# stm32_mcu.net
KiCad netlist of a schematic drawn in Altium Designer
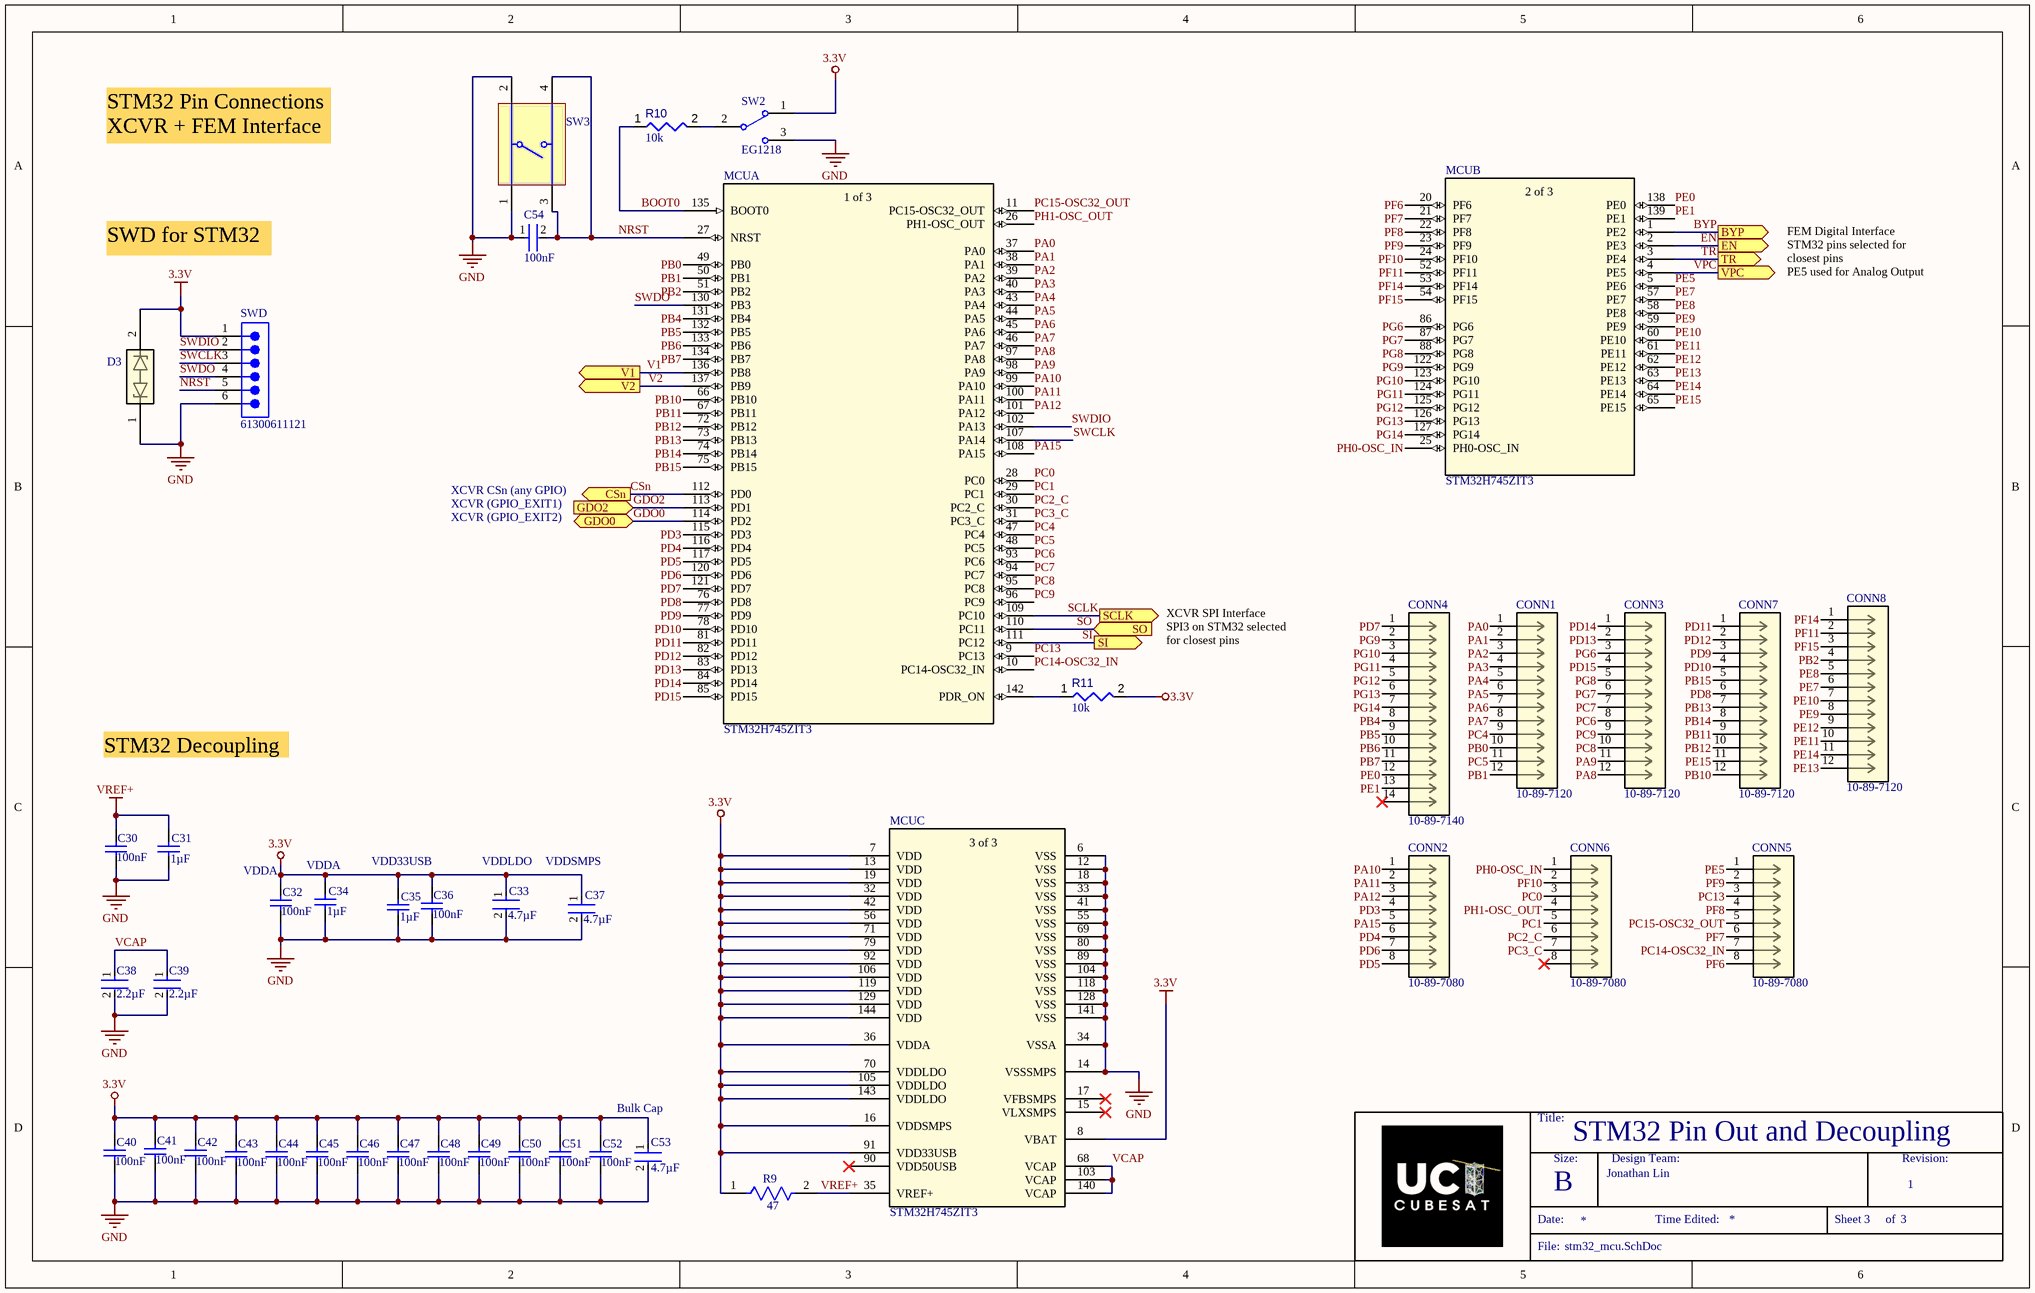
[diagram p0: stm32_mcu.SchDoc]

(export (version "E")
  (design (tool "Eeschema 10.0.6"))
  (components
    (comp (ref "C30")
      (value "100nF")
      (footprint "CAPC2013X135X45ML10T25")
      (fields (field (name "Comment") "GRM21BR72A104KAC4L"))
      (libsource (lib "University of California Irvine") (part "CAP"))
    )
    (comp (ref "C31")
      (value "1µF")
      (footprint "CAPC2013X135X45LL10T25")
      (fields (field (name "Comment") "GRM21BR71C105KA01L"))
      (libsource (lib "University of California Irvine") (part "CAP-NP-2"))
    )
    (comp (ref "C32")
      (value "100nF")
      (footprint "CAPC2013X135X45ML10T25")
      (fields (field (name "Comment") "GRM21BR72A104KAC4L"))
      (libsource (lib "University of California Irvine") (part "CAP"))
    )
    (comp (ref "C33")
      (value "4.7µF")
      (footprint "FP-GRM21B-0_2-e0_2_0_7-MFG")
      (fields (field (name "Comment") "GRM21BZ7YA475KE15K"))
      (libsource (lib "University of California Irvine") (part "b4654b650e69147ec39a6b967a45e02"))
    )
    (comp (ref "C34")
      (value "1µF")
      (footprint "CAPC2013X135X45LL10T25")
      (fields (field (name "Comment") "GRM21BR71C105KA01L"))
      (libsource (lib "University of California Irvine") (part "CAP-NP-2"))
    )
    (comp (ref "C35")
      (value "1µF")
      (footprint "CAPC2013X135X45LL10T25")
      (fields (field (name "Comment") "GRM21BR71C105KA01L"))
      (libsource (lib "University of California Irvine") (part "CAP-NP-2"))
    )
    (comp (ref "C36")
      (value "100nF")
      (footprint "CAPC2013X135X45ML10T25")
      (fields (field (name "Comment") "GRM21BR72A104KAC4L"))
      (libsource (lib "University of California Irvine") (part "CAP"))
    )
    (comp (ref "C37")
      (value "4.7µF")
      (footprint "FP-GRM21B-0_2-e0_2_0_7-MFG")
      (fields (field (name "Comment") "GRM21BZ7YA475KE15K"))
      (libsource (lib "University of California Irvine") (part "b4654b650e69147ec39a6b967a45e02"))
    )
    (comp (ref "C38")
      (value "2.2µF")
      (footprint "FP-GRM21B-0_15-IPC_A")
      (fields (field (name "Comment") "GRM21BR71E225KE11L"))
      (libsource (lib "University of California Irvine") (part "b4654b650e69147ec39a6b967a45e02"))
    )
    (comp (ref "C39")
      (value "2.2µF")
      (footprint "FP-GRM21B-0_15-IPC_A")
      (fields (field (name "Comment") "GRM21BR71E225KE11L"))
      (libsource (lib "University of California Irvine") (part "b4654b650e69147ec39a6b967a45e02"))
    )
    (comp (ref "C40")
      (value "100nF")
      (footprint "CAPC2013X135X45ML10T25")
      (fields (field (name "Comment") "GRM21BR72A104KAC4L"))
      (libsource (lib "University of California Irvine") (part "CAP"))
    )
    (comp (ref "C41")
      (value "100nF")
      (footprint "CAPC2013X135X45ML10T25")
      (fields (field (name "Comment") "GRM21BR72A104KAC4L"))
      (libsource (lib "University of California Irvine") (part "CAP"))
    )
    (comp (ref "C42")
      (value "100nF")
      (footprint "CAPC2013X135X45ML10T25")
      (fields (field (name "Comment") "GRM21BR72A104KAC4L"))
      (libsource (lib "University of California Irvine") (part "CAP"))
    )
    (comp (ref "C43")
      (value "100nF")
      (footprint "CAPC2013X135X45ML10T25")
      (fields (field (name "Comment") "GRM21BR72A104KAC4L"))
      (libsource (lib "University of California Irvine") (part "CAP"))
    )
    (comp (ref "C44")
      (value "100nF")
      (footprint "CAPC2013X135X45ML10T25")
      (fields (field (name "Comment") "GRM21BR72A104KAC4L"))
      (libsource (lib "University of California Irvine") (part "CAP"))
    )
    (comp (ref "C45")
      (value "100nF")
      (footprint "CAPC2013X135X45ML10T25")
      (fields (field (name "Comment") "GRM21BR72A104KAC4L"))
      (libsource (lib "University of California Irvine") (part "CAP"))
    )
    (comp (ref "C46")
      (value "100nF")
      (footprint "CAPC2013X135X45ML10T25")
      (fields (field (name "Comment") "GRM21BR72A104KAC4L"))
      (libsource (lib "University of California Irvine") (part "CAP"))
    )
    (comp (ref "C47")
      (value "100nF")
      (footprint "CAPC2013X135X45ML10T25")
      (fields (field (name "Comment") "GRM21BR72A104KAC4L"))
      (libsource (lib "University of California Irvine") (part "CAP"))
    )
    (comp (ref "C48")
      (value "100nF")
      (footprint "CAPC2013X135X45ML10T25")
      (fields (field (name "Comment") "GRM21BR72A104KAC4L"))
      (libsource (lib "University of California Irvine") (part "CAP"))
    )
    (comp (ref "C49")
      (value "100nF")
      (footprint "CAPC2013X135X45ML10T25")
      (fields (field (name "Comment") "GRM21BR72A104KAC4L"))
      (libsource (lib "University of California Irvine") (part "CAP"))
    )
    (comp (ref "C50")
      (value "100nF")
      (footprint "CAPC2013X135X45ML10T25")
      (fields (field (name "Comment") "GRM21BR72A104KAC4L"))
      (libsource (lib "University of California Irvine") (part "CAP"))
    )
    (comp (ref "C51")
      (value "100nF")
      (footprint "CAPC2013X135X45ML10T25")
      (fields (field (name "Comment") "GRM21BR72A104KAC4L"))
      (libsource (lib "University of California Irvine") (part "CAP"))
    )
    (comp (ref "C52")
      (value "100nF")
      (footprint "CAPC2013X135X45ML10T25")
      (fields (field (name "Comment") "GRM21BR72A104KAC4L"))
      (libsource (lib "University of California Irvine") (part "CAP"))
    )
    (comp (ref "C53")
      (value "4.7µF")
      (footprint "FP-GRM21B-0_2-e0_2_0_7-MFG")
      (fields (field (name "Comment") "GRM21BZ7YA475KE15K"))
      (libsource (lib "University of California Irvine") (part "b4654b650e69147ec39a6b967a45e02"))
    )
    (comp (ref "C54")
      (value "100nF")
      (footprint "FP-C0805C-DN-IPC_A")
      (fields (field (name "Comment") "C0805C104K5RACTU"))
      (libsource (lib "University of California Irvine") (part "b4654b650e69147ec39a6b967a45e02"))
    )
    (comp (ref "CONN1")
      (value "10-89-7120")
      (footprint "CONN12_0010897120_MOL")
      (libsource (lib "University of California Irvine") (part "10-89-7120-Symbol-1"))
    )
    (comp (ref "CONN2")
      (value "10-89-7080")
      (footprint "CONN08_0010897080_MOL")
      (libsource (lib "University of California Irvine") (part "10-89-7080-Symbol-1"))
    )
    (comp (ref "CONN3")
      (value "10-89-7120")
      (footprint "CONN12_0010897120_MOL")
      (libsource (lib "University of California Irvine") (part "10-89-7120-Symbol-1"))
    )
    (comp (ref "CONN4")
      (value "10-89-7140")
      (footprint "CONN14_0010897140_MOL")
      (libsource (lib "University of California Irvine") (part "10-89-7140-Symbol-1"))
    )
    (comp (ref "CONN5")
      (value "10-89-7080")
      (footprint "CONN08_0010897080_MOL")
      (libsource (lib "University of California Irvine") (part "10-89-7080-Symbol-1"))
    )
    (comp (ref "CONN6")
      (value "10-89-7080")
      (footprint "CONN08_0010897080_MOL")
      (libsource (lib "University of California Irvine") (part "10-89-7080-Symbol-1"))
    )
    (comp (ref "CONN7")
      (value "10-89-7120")
      (footprint "CONN12_0010897120_MOL")
      (libsource (lib "University of California Irvine") (part "10-89-7120-Symbol-1"))
    )
    (comp (ref "CONN8")
      (value "10-89-7120")
      (footprint "CONN12_0010897120_MOL")
      (libsource (lib "University of California Irvine") (part "10-89-7120-Symbol-1"))
    )
    (comp (ref "D3")
      (value "PESD3V3Z1BCSFYL")
      (footprint "SOD962-2_DSN0603-2_NEX")
      (description "PESD3V3Zxx: 6.8 V 15 A 0.45 pF Bidirectional ESD Protection Diode - DSN0603-2")
      (libsource (lib "University of California Irvine") (part "PESD3V3Z1BCSFYL-Symbol-1"))
    )
    (comp (ref "MCU")
      (value "STM32H745ZIT3")
      (footprint "LQFP-144")
      (description "No Description Available")
      (libsource (lib "University of California Irvine") (part "STM32H745ZIT3"))
    )
    (comp (ref "R9")
      (value "47")
      (footprint "FP-RMCF1206-IPC_B")
      (fields
        (field (name "POWER") "250mW")
        (field (name "TOLERANCE") "5%")
        (field (name "Comment") "RMCF1206JT47R0")
      )
      (libsource (lib "University of California Irvine") (part "1029c3af85768c4190bb7ad29bc67b5"))
    )
    (comp (ref "R10")
      (value "10k")
      (footprint "RESC3216X60X45ML15T20")
      (fields
        (field (name "TOLERANCE") "1%")
        (field (name "POWER") "250mW")
        (field (name "Comment") "RC0805FR-0710KL")
      )
      (libsource (lib "University of California Irvine") (part "RES-2"))
    )
    (comp (ref "R11")
      (value "10k")
      (footprint "RESC3216X60X45ML15T20")
      (description "Chip Resistor, 10 KOhm, +/- 1%, 0.25 W, -55 to 155 degC, 1206 (3216 Metric)")
      (fields (field (name "TOLERANCE") "1%") (field (name "POWER") "250mW"))
      (libsource (lib "University of California Irvine") (part "RES-2"))
    )
    (comp (ref "SW2")
      (value "EG1218")
      (footprint "ESWI-EG1218_V")
      (description "Slide Switch, SPDT, 500 V, -20 to 70 degC, 3-Pin THD, RoHS, Bulk")
      (fields (field (name "MANUFACTURER") "E-Switch"))
      (libsource (lib "University of California Irvine") (part "SW-SPDT-3_B"))
    )
    (comp (ref "SW3")
      (value "1825910-6 Tact Switch")
      (footprint "TECO-1825910-6_V")
      (libsource (lib "University of California Irvine") (part "SW-SPST-4_A"))
    )
    (comp (ref "SWD")
      (value "61300611121")
      (footprint "61300611121")
      (libsource (lib "University of California Irvine") (part "Header_Male_1R_06P"))
    )
  )
  (nets
    (net (code "1") (name "/BOOT0") (class "Default")
      (node (ref "MCU") (pin "135") (pinfunction "BOOT0_135") (pintype "input"))
      (node (ref "R10") (pin "1") (pinfunction "1_1") (pintype "passive"))
    )
    (net (code "2") (name "/BYP") (class "Default")
      (node (ref "MCU") (pin "1") (pinfunction "PE2_1") (pintype "bidirectional"))
    )
    (net (code "3") (name "/CSn") (class "Default")
      (node (ref "MCU") (pin "112") (pinfunction "PD0_112") (pintype "bidirectional"))
    )
    (net (code "4") (name "/EN") (class "Default")
      (node (ref "MCU") (pin "2") (pinfunction "PE3_2") (pintype "bidirectional"))
    )
    (net (code "5") (name "/GDO0") (class "Default")
      (node (ref "MCU") (pin "114") (pinfunction "PD2_114") (pintype "bidirectional"))
    )
    (net (code "6") (name "/GDO2") (class "Default")
      (node (ref "MCU") (pin "113") (pinfunction "PD1_113") (pintype "bidirectional"))
    )
    (net (code "7") (name "/NRST") (class "Default")
      (node (ref "C54") (pin "2") (pinfunction "2_2") (pintype "passive"))
      (node (ref "MCU") (pin "27") (pinfunction "NRST_27") (pintype "bidirectional"))
      (node (ref "SW3") (pin "3") (pinfunction "3_3") (pintype "passive"))
      (node (ref "SW3") (pin "4") (pinfunction "4_4") (pintype "passive"))
      (node (ref "SWD") (pin "5") (pinfunction "5_5") (pintype "passive"))
    )
    (net (code "8") (name "/PA0") (class "Default")
      (node (ref "CONN1") (pin "1") (pinfunction "1_1") (pintype "passive"))
      (node (ref "MCU") (pin "37") (pinfunction "PA0_37") (pintype "bidirectional"))
    )
    (net (code "9") (name "/PA1") (class "Default")
      (node (ref "CONN1") (pin "2") (pinfunction "2_2") (pintype "passive"))
      (node (ref "MCU") (pin "38") (pinfunction "PA1_38") (pintype "bidirectional"))
    )
    (net (code "10") (name "/PA2") (class "Default")
      (node (ref "CONN1") (pin "3") (pinfunction "3_3") (pintype "passive"))
      (node (ref "MCU") (pin "39") (pinfunction "PA2_39") (pintype "bidirectional"))
    )
    (net (code "11") (name "/PA3") (class "Default")
      (node (ref "CONN1") (pin "4") (pinfunction "4_4") (pintype "passive"))
      (node (ref "MCU") (pin "40") (pinfunction "PA3_40") (pintype "bidirectional"))
    )
    (net (code "12") (name "/PA4") (class "Default")
      (node (ref "CONN1") (pin "5") (pinfunction "5_5") (pintype "passive"))
      (node (ref "MCU") (pin "43") (pinfunction "PA4_43") (pintype "bidirectional"))
    )
    (net (code "13") (name "/PA5") (class "Default")
      (node (ref "CONN1") (pin "6") (pinfunction "6_6") (pintype "passive"))
      (node (ref "MCU") (pin "44") (pinfunction "PA5_44") (pintype "bidirectional"))
    )
    (net (code "14") (name "/PA6") (class "Default")
      (node (ref "CONN1") (pin "7") (pinfunction "7_7") (pintype "passive"))
      (node (ref "MCU") (pin "45") (pinfunction "PA6_45") (pintype "bidirectional"))
    )
    (net (code "15") (name "/PA7") (class "Default")
      (node (ref "CONN1") (pin "8") (pinfunction "8_8") (pintype "passive"))
      (node (ref "MCU") (pin "46") (pinfunction "PA7_46") (pintype "bidirectional"))
    )
    (net (code "16") (name "/PA8") (class "Default")
      (node (ref "CONN3") (pin "12") (pinfunction "12_12") (pintype "passive"))
      (node (ref "MCU") (pin "97") (pinfunction "PA8_97") (pintype "bidirectional"))
    )
    (net (code "17") (name "/PA9") (class "Default")
      (node (ref "CONN3") (pin "11") (pinfunction "11_11") (pintype "passive"))
      (node (ref "MCU") (pin "98") (pinfunction "PA9_98") (pintype "bidirectional"))
    )
    (net (code "18") (name "/PA10") (class "Default")
      (node (ref "CONN2") (pin "1") (pinfunction "1_1") (pintype "passive"))
      (node (ref "MCU") (pin "99") (pinfunction "PA10_99") (pintype "bidirectional"))
    )
    (net (code "19") (name "/PA11") (class "Default")
      (node (ref "CONN2") (pin "2") (pinfunction "2_2") (pintype "passive"))
      (node (ref "MCU") (pin "100") (pinfunction "PA11_100") (pintype "bidirectional"))
    )
    (net (code "20") (name "/PA12") (class "Default")
      (node (ref "CONN2") (pin "3") (pinfunction "3_3") (pintype "passive"))
      (node (ref "MCU") (pin "101") (pinfunction "PA12_101") (pintype "bidirectional"))
    )
    (net (code "21") (name "/PA15") (class "Default")
      (node (ref "CONN2") (pin "5") (pinfunction "5_5") (pintype "passive"))
      (node (ref "MCU") (pin "108") (pinfunction "PA15_108") (pintype "bidirectional"))
    )
    (net (code "22") (name "/PB0") (class "Default")
      (node (ref "CONN1") (pin "10") (pinfunction "10_10") (pintype "passive"))
      (node (ref "MCU") (pin "49") (pinfunction "PB0_49") (pintype "bidirectional"))
    )
    (net (code "23") (name "/PB1") (class "Default")
      (node (ref "CONN1") (pin "12") (pinfunction "12_12") (pintype "passive"))
      (node (ref "MCU") (pin "50") (pinfunction "PB1_50") (pintype "bidirectional"))
    )
    (net (code "24") (name "/PB2") (class "Default")
      (node (ref "CONN8") (pin "4") (pinfunction "4_4") (pintype "passive"))
      (node (ref "MCU") (pin "51") (pinfunction "PB2_51") (pintype "bidirectional"))
    )
    (net (code "25") (name "/PB4") (class "Default")
      (node (ref "CONN4") (pin "8") (pinfunction "8_8") (pintype "passive"))
      (node (ref "MCU") (pin "131") (pinfunction "PB4_131") (pintype "bidirectional"))
    )
    (net (code "26") (name "/PB5") (class "Default")
      (node (ref "CONN4") (pin "9") (pinfunction "9_9") (pintype "passive"))
      (node (ref "MCU") (pin "132") (pinfunction "PB5_132") (pintype "bidirectional"))
    )
    (net (code "27") (name "/PB6") (class "Default")
      (node (ref "CONN4") (pin "10") (pinfunction "10_10") (pintype "passive"))
      (node (ref "MCU") (pin "133") (pinfunction "PB6_133") (pintype "bidirectional"))
    )
    (net (code "28") (name "/PB7") (class "Default")
      (node (ref "CONN4") (pin "11") (pinfunction "11_11") (pintype "passive"))
      (node (ref "MCU") (pin "134") (pinfunction "PB7_134") (pintype "bidirectional"))
    )
    (net (code "29") (name "/PB10") (class "Default")
      (node (ref "CONN7") (pin "12") (pinfunction "12_12") (pintype "passive"))
      (node (ref "MCU") (pin "66") (pinfunction "PB10_66") (pintype "bidirectional"))
    )
    (net (code "30") (name "/PB11") (class "Default")
      (node (ref "CONN7") (pin "9") (pinfunction "9_9") (pintype "passive"))
      (node (ref "MCU") (pin "67") (pinfunction "PB11_67") (pintype "bidirectional"))
    )
    (net (code "31") (name "/PB12") (class "Default")
      (node (ref "CONN7") (pin "10") (pinfunction "10_10") (pintype "passive"))
      (node (ref "MCU") (pin "72") (pinfunction "PB12_72") (pintype "bidirectional"))
    )
    (net (code "32") (name "/PB13") (class "Default")
      (node (ref "CONN7") (pin "7") (pinfunction "7_7") (pintype "passive"))
      (node (ref "MCU") (pin "73") (pinfunction "PB13_73") (pintype "bidirectional"))
    )
    (net (code "33") (name "/PB14") (class "Default")
      (node (ref "CONN7") (pin "8") (pinfunction "8_8") (pintype "passive"))
      (node (ref "MCU") (pin "74") (pinfunction "PB14_74") (pintype "bidirectional"))
    )
    (net (code "34") (name "/PB15") (class "Default")
      (node (ref "CONN7") (pin "5") (pinfunction "5_5") (pintype "passive"))
      (node (ref "MCU") (pin "75") (pinfunction "PB15_75") (pintype "bidirectional"))
    )
    (net (code "35") (name "/PC0") (class "Default")
      (node (ref "CONN6") (pin "3") (pinfunction "3_3") (pintype "passive"))
      (node (ref "MCU") (pin "28") (pinfunction "PC0_28") (pintype "bidirectional"))
    )
    (net (code "36") (name "/PC1") (class "Default")
      (node (ref "CONN6") (pin "5") (pinfunction "5_5") (pintype "passive"))
      (node (ref "MCU") (pin "29") (pinfunction "PC1_29") (pintype "bidirectional"))
    )
    (net (code "37") (name "/PC2_C") (class "Default")
      (node (ref "CONN6") (pin "6") (pinfunction "6_6") (pintype "passive"))
      (node (ref "MCU") (pin "30") (pinfunction "PC2_C_30") (pintype "bidirectional"))
    )
    (net (code "38") (name "/PC3_C") (class "Default")
      (node (ref "CONN6") (pin "7") (pinfunction "7_7") (pintype "passive"))
      (node (ref "MCU") (pin "31") (pinfunction "PC3_C_31") (pintype "bidirectional"))
    )
    (net (code "39") (name "/PC4") (class "Default")
      (node (ref "CONN1") (pin "9") (pinfunction "9_9") (pintype "passive"))
      (node (ref "MCU") (pin "47") (pinfunction "PC4_47") (pintype "bidirectional"))
    )
    (net (code "40") (name "/PC5") (class "Default")
      (node (ref "CONN1") (pin "11") (pinfunction "11_11") (pintype "passive"))
      (node (ref "MCU") (pin "48") (pinfunction "PC5_48") (pintype "bidirectional"))
    )
    (net (code "41") (name "/PC6") (class "Default")
      (node (ref "CONN3") (pin "8") (pinfunction "8_8") (pintype "passive"))
      (node (ref "MCU") (pin "93") (pinfunction "PC6_93") (pintype "bidirectional"))
    )
    (net (code "42") (name "/PC7") (class "Default")
      (node (ref "CONN3") (pin "7") (pinfunction "7_7") (pintype "passive"))
      (node (ref "MCU") (pin "94") (pinfunction "PC7_94") (pintype "bidirectional"))
    )
    (net (code "43") (name "/PC8") (class "Default")
      (node (ref "CONN3") (pin "10") (pinfunction "10_10") (pintype "passive"))
      (node (ref "MCU") (pin "95") (pinfunction "PC8_95") (pintype "bidirectional"))
    )
    (net (code "44") (name "/PC9") (class "Default")
      (node (ref "CONN3") (pin "9") (pinfunction "9_9") (pintype "passive"))
      (node (ref "MCU") (pin "96") (pinfunction "PC9_96") (pintype "bidirectional"))
    )
    (net (code "45") (name "/PC13") (class "Default")
      (node (ref "CONN5") (pin "3") (pinfunction "3_3") (pintype "passive"))
      (node (ref "MCU") (pin "9") (pinfunction "PC13_9") (pintype "bidirectional"))
    )
    (net (code "46") (name "/PC14-OSC32_IN") (class "Default")
      (node (ref "CONN5") (pin "7") (pinfunction "7_7") (pintype "passive"))
      (node (ref "MCU") (pin "10") (pinfunction "PC14-OSC32_IN_10") (pintype "bidirectional"))
    )
    (net (code "47") (name "/PC15-OSC32_OUT") (class "Default")
      (node (ref "CONN5") (pin "5") (pinfunction "5_5") (pintype "passive"))
      (node (ref "MCU") (pin "11") (pinfunction "PC15-OSC32_OUT_11") (pintype "bidirectional"))
    )
    (net (code "48") (name "/PD3") (class "Default")
      (node (ref "CONN2") (pin "4") (pinfunction "4_4") (pintype "passive"))
      (node (ref "MCU") (pin "115") (pinfunction "PD3_115") (pintype "bidirectional"))
    )
    (net (code "49") (name "/PD4") (class "Default")
      (node (ref "CONN2") (pin "6") (pinfunction "6_6") (pintype "passive"))
      (node (ref "MCU") (pin "116") (pinfunction "PD4_116") (pintype "bidirectional"))
    )
    (net (code "50") (name "/PD5") (class "Default")
      (node (ref "CONN2") (pin "8") (pinfunction "8_8") (pintype "passive"))
      (node (ref "MCU") (pin "117") (pinfunction "PD5_117") (pintype "bidirectional"))
    )
    (net (code "51") (name "/PD6") (class "Default")
      (node (ref "CONN2") (pin "7") (pinfunction "7_7") (pintype "passive"))
      (node (ref "MCU") (pin "120") (pinfunction "PD6_120") (pintype "bidirectional"))
    )
    (net (code "52") (name "/PD7") (class "Default")
      (node (ref "CONN4") (pin "1") (pinfunction "1_1") (pintype "passive"))
      (node (ref "MCU") (pin "121") (pinfunction "PD7_121") (pintype "bidirectional"))
    )
    (net (code "53") (name "/PD8") (class "Default")
      (node (ref "CONN7") (pin "6") (pinfunction "6_6") (pintype "passive"))
      (node (ref "MCU") (pin "76") (pinfunction "PD8_76") (pintype "bidirectional"))
    )
    (net (code "54") (name "/PD9") (class "Default")
      (node (ref "CONN7") (pin "3") (pinfunction "3_3") (pintype "passive"))
      (node (ref "MCU") (pin "77") (pinfunction "PD9_77") (pintype "bidirectional"))
    )
    (net (code "55") (name "/PD10") (class "Default")
      (node (ref "CONN7") (pin "4") (pinfunction "4_4") (pintype "passive"))
      (node (ref "MCU") (pin "78") (pinfunction "PD10_78") (pintype "bidirectional"))
    )
    (net (code "56") (name "/PD11") (class "Default")
      (node (ref "CONN7") (pin "1") (pinfunction "1_1") (pintype "passive"))
      (node (ref "MCU") (pin "81") (pinfunction "PD11_81") (pintype "bidirectional"))
    )
    (net (code "57") (name "/PD12") (class "Default")
      (node (ref "CONN7") (pin "2") (pinfunction "2_2") (pintype "passive"))
      (node (ref "MCU") (pin "82") (pinfunction "PD12_82") (pintype "bidirectional"))
    )
    (net (code "58") (name "/PD13") (class "Default")
      (node (ref "CONN3") (pin "2") (pinfunction "2_2") (pintype "passive"))
      (node (ref "MCU") (pin "83") (pinfunction "PD13_83") (pintype "bidirectional"))
    )
    (net (code "59") (name "/PD14") (class "Default")
      (node (ref "CONN3") (pin "1") (pinfunction "1_1") (pintype "passive"))
      (node (ref "MCU") (pin "84") (pinfunction "PD14_84") (pintype "bidirectional"))
    )
    (net (code "60") (name "/PD15") (class "Default")
      (node (ref "CONN3") (pin "4") (pinfunction "4_4") (pintype "passive"))
      (node (ref "MCU") (pin "85") (pinfunction "PD15_85") (pintype "bidirectional"))
    )
    (net (code "61") (name "/PE0") (class "Default")
      (node (ref "CONN4") (pin "12") (pinfunction "12_12") (pintype "passive"))
      (node (ref "MCU") (pin "138") (pinfunction "PE0_138") (pintype "bidirectional"))
    )
    (net (code "62") (name "/PE1") (class "Default")
      (node (ref "CONN4") (pin "13") (pinfunction "13_13") (pintype "passive"))
      (node (ref "MCU") (pin "139") (pinfunction "PE1_139") (pintype "bidirectional"))
    )
    (net (code "63") (name "/PE5") (class "Default")
      (node (ref "CONN5") (pin "1") (pinfunction "1_1") (pintype "passive"))
      (node (ref "MCU") (pin "5") (pinfunction "PE6_5") (pintype "bidirectional"))
    )
    (net (code "64") (name "/PE7") (class "Default")
      (node (ref "CONN8") (pin "6") (pinfunction "6_6") (pintype "passive"))
      (node (ref "MCU") (pin "57") (pinfunction "PE7_57") (pintype "bidirectional"))
    )
    (net (code "65") (name "/PE8") (class "Default")
      (node (ref "CONN8") (pin "5") (pinfunction "5_5") (pintype "passive"))
      (node (ref "MCU") (pin "58") (pinfunction "PE8_58") (pintype "bidirectional"))
    )
    (net (code "66") (name "/PE9") (class "Default")
      (node (ref "CONN8") (pin "8") (pinfunction "8_8") (pintype "passive"))
      (node (ref "MCU") (pin "59") (pinfunction "PE9_59") (pintype "bidirectional"))
    )
    (net (code "67") (name "/PE10") (class "Default")
      (node (ref "CONN8") (pin "7") (pinfunction "7_7") (pintype "passive"))
      (node (ref "MCU") (pin "60") (pinfunction "PE10_60") (pintype "bidirectional"))
    )
    (net (code "68") (name "/PE11") (class "Default")
      (node (ref "CONN8") (pin "10") (pinfunction "10_10") (pintype "passive"))
      (node (ref "MCU") (pin "61") (pinfunction "PE11_61") (pintype "bidirectional"))
    )
    (net (code "69") (name "/PE12") (class "Default")
      (node (ref "CONN8") (pin "9") (pinfunction "9_9") (pintype "passive"))
      (node (ref "MCU") (pin "62") (pinfunction "PE12_62") (pintype "bidirectional"))
    )
    (net (code "70") (name "/PE13") (class "Default")
      (node (ref "CONN8") (pin "12") (pinfunction "12_12") (pintype "passive"))
      (node (ref "MCU") (pin "63") (pinfunction "PE13_63") (pintype "bidirectional"))
    )
    (net (code "71") (name "/PE14") (class "Default")
      (node (ref "CONN8") (pin "11") (pinfunction "11_11") (pintype "passive"))
      (node (ref "MCU") (pin "64") (pinfunction "PE14_64") (pintype "bidirectional"))
    )
    (net (code "72") (name "/PE15") (class "Default")
      (node (ref "CONN7") (pin "11") (pinfunction "11_11") (pintype "passive"))
      (node (ref "MCU") (pin "65") (pinfunction "PE15_65") (pintype "bidirectional"))
    )
    (net (code "73") (name "/PF6") (class "Default")
      (node (ref "CONN5") (pin "8") (pinfunction "8_8") (pintype "passive"))
      (node (ref "MCU") (pin "20") (pinfunction "PF6_20") (pintype "bidirectional"))
    )
    (net (code "74") (name "/PF7") (class "Default")
      (node (ref "CONN5") (pin "6") (pinfunction "6_6") (pintype "passive"))
      (node (ref "MCU") (pin "21") (pinfunction "PF7_21") (pintype "bidirectional"))
    )
    (net (code "75") (name "/PF8") (class "Default")
      (node (ref "CONN5") (pin "4") (pinfunction "4_4") (pintype "passive"))
      (node (ref "MCU") (pin "22") (pinfunction "PF8_22") (pintype "bidirectional"))
    )
    (net (code "76") (name "/PF9") (class "Default")
      (node (ref "CONN5") (pin "2") (pinfunction "2_2") (pintype "passive"))
      (node (ref "MCU") (pin "23") (pinfunction "PF9_23") (pintype "bidirectional"))
    )
    (net (code "77") (name "/PF10") (class "Default")
      (node (ref "CONN6") (pin "2") (pinfunction "2_2") (pintype "passive"))
      (node (ref "MCU") (pin "24") (pinfunction "PF10_24") (pintype "bidirectional"))
    )
    (net (code "78") (name "/PF11") (class "Default")
      (node (ref "CONN8") (pin "2") (pinfunction "2_2") (pintype "passive"))
      (node (ref "MCU") (pin "52") (pinfunction "PF11_52") (pintype "bidirectional"))
    )
    (net (code "79") (name "/PF14") (class "Default")
      (node (ref "CONN8") (pin "1") (pinfunction "1_1") (pintype "passive"))
      (node (ref "MCU") (pin "53") (pinfunction "PF14_53") (pintype "bidirectional"))
    )
    (net (code "80") (name "/PF15") (class "Default")
      (node (ref "CONN8") (pin "3") (pinfunction "3_3") (pintype "passive"))
      (node (ref "MCU") (pin "54") (pinfunction "PF15_54") (pintype "bidirectional"))
    )
    (net (code "81") (name "/PG6") (class "Default")
      (node (ref "CONN3") (pin "3") (pinfunction "3_3") (pintype "passive"))
      (node (ref "MCU") (pin "86") (pinfunction "PG6_86") (pintype "bidirectional"))
    )
    (net (code "82") (name "/PG7") (class "Default")
      (node (ref "CONN3") (pin "6") (pinfunction "6_6") (pintype "passive"))
      (node (ref "MCU") (pin "87") (pinfunction "PG7_87") (pintype "bidirectional"))
    )
    (net (code "83") (name "/PG8") (class "Default")
      (node (ref "CONN3") (pin "5") (pinfunction "5_5") (pintype "passive"))
      (node (ref "MCU") (pin "88") (pinfunction "PG8_88") (pintype "bidirectional"))
    )
    (net (code "84") (name "/PG9") (class "Default")
      (node (ref "CONN4") (pin "2") (pinfunction "2_2") (pintype "passive"))
      (node (ref "MCU") (pin "122") (pinfunction "PG9_122") (pintype "bidirectional"))
    )
    (net (code "85") (name "/PG10") (class "Default")
      (node (ref "CONN4") (pin "3") (pinfunction "3_3") (pintype "passive"))
      (node (ref "MCU") (pin "123") (pinfunction "PG10_123") (pintype "bidirectional"))
    )
    (net (code "86") (name "/PG11") (class "Default")
      (node (ref "CONN4") (pin "4") (pinfunction "4_4") (pintype "passive"))
      (node (ref "MCU") (pin "124") (pinfunction "PG11_124") (pintype "bidirectional"))
    )
    (net (code "87") (name "/PG12") (class "Default")
      (node (ref "CONN4") (pin "5") (pinfunction "5_5") (pintype "passive"))
      (node (ref "MCU") (pin "125") (pinfunction "PG12_125") (pintype "bidirectional"))
    )
    (net (code "88") (name "/PG13") (class "Default")
      (node (ref "CONN4") (pin "6") (pinfunction "6_6") (pintype "passive"))
      (node (ref "MCU") (pin "126") (pinfunction "PG13_126") (pintype "bidirectional"))
    )
    (net (code "89") (name "/PG14") (class "Default")
      (node (ref "CONN4") (pin "7") (pinfunction "7_7") (pintype "passive"))
      (node (ref "MCU") (pin "127") (pinfunction "PG14_127") (pintype "bidirectional"))
    )
    (net (code "90") (name "/PH0-OSC_IN") (class "Default")
      (node (ref "CONN6") (pin "1") (pinfunction "1_1") (pintype "passive"))
      (node (ref "MCU") (pin "25") (pinfunction "PH0-OSC_IN_25") (pintype "bidirectional"))
    )
    (net (code "91") (name "/PH1-OSC_OUT") (class "Default")
      (node (ref "CONN6") (pin "4") (pinfunction "4_4") (pintype "passive"))
      (node (ref "MCU") (pin "26") (pinfunction "PH1-OSC_OUT_26") (pintype "bidirectional"))
    )
    (net (code "92") (name "/SCLK") (class "Default")
      (node (ref "MCU") (pin "109") (pinfunction "PC10_109") (pintype "bidirectional"))
    )
    (net (code "93") (name "/SI") (class "Default")
      (node (ref "MCU") (pin "111") (pinfunction "PC12_111") (pintype "bidirectional"))
    )
    (net (code "94") (name "/SO") (class "Default")
      (node (ref "MCU") (pin "110") (pinfunction "PC11_110") (pintype "bidirectional"))
    )
    (net (code "95") (name "/SWCLK") (class "Default")
      (node (ref "MCU") (pin "107") (pinfunction "PA14_107") (pintype "bidirectional"))
      (node (ref "SWD") (pin "3") (pinfunction "3_3") (pintype "passive"))
    )
    (net (code "96") (name "/SWDIO") (class "Default")
      (node (ref "MCU") (pin "102") (pinfunction "PA13_102") (pintype "bidirectional"))
      (node (ref "SWD") (pin "2") (pinfunction "2_2") (pintype "passive"))
    )
    (net (code "97") (name "/SWDO") (class "Default")
      (node (ref "MCU") (pin "130") (pinfunction "PB3_130") (pintype "bidirectional"))
      (node (ref "SWD") (pin "4") (pinfunction "4_4") (pintype "passive"))
    )
    (net (code "98") (name "/TR") (class "Default")
      (node (ref "MCU") (pin "3") (pinfunction "PE4_3") (pintype "bidirectional"))
    )
    (net (code "99") (name "/V1") (class "Default")
      (node (ref "MCU") (pin "136") (pinfunction "PB8_136") (pintype "bidirectional"))
    )
    (net (code "100") (name "/V2") (class "Default")
      (node (ref "MCU") (pin "137") (pinfunction "PB9_137") (pintype "bidirectional"))
    )
    (net (code "101") (name "/VCAP") (class "Default")
      (node (ref "C38") (pin "1") (pinfunction "1_1") (pintype "passive"))
      (node (ref "C39") (pin "1") (pinfunction "1_1") (pintype "passive"))
      (node (ref "MCU") (pin "103") (pinfunction "VCAP_103") (pintype "power_in"))
      (node (ref "MCU") (pin "140") (pinfunction "VCAP_140") (pintype "power_in"))
      (node (ref "MCU") (pin "68") (pinfunction "VCAP_68") (pintype "power_in"))
    )
    (net (code "102") (name "/VPC") (class "Default")
      (node (ref "MCU") (pin "4") (pinfunction "PE5_4") (pintype "bidirectional"))
    )
    (net (code "103") (name "3.3V") (class "Default")
      (node (ref "C32") (pin "2") (pinfunction "2_2") (pintype "passive"))
      (node (ref "C33") (pin "1") (pinfunction "1_1") (pintype "passive"))
      (node (ref "C34") (pin "2") (pinfunction "2_2") (pintype "passive"))
      (node (ref "C35") (pin "2") (pinfunction "2_2") (pintype "passive"))
      (node (ref "C36") (pin "2") (pinfunction "2_2") (pintype "passive"))
      (node (ref "C37") (pin "1") (pinfunction "1_1") (pintype "passive"))
      (node (ref "C40") (pin "2") (pinfunction "2_2") (pintype "passive"))
      (node (ref "C41") (pin "2") (pinfunction "2_2") (pintype "passive"))
      (node (ref "C42") (pin "2") (pinfunction "2_2") (pintype "passive"))
      (node (ref "C43") (pin "2") (pinfunction "2_2") (pintype "passive"))
      (node (ref "C44") (pin "2") (pinfunction "2_2") (pintype "passive"))
      (node (ref "C45") (pin "2") (pinfunction "2_2") (pintype "passive"))
      (node (ref "C46") (pin "2") (pinfunction "2_2") (pintype "passive"))
      (node (ref "C47") (pin "2") (pinfunction "2_2") (pintype "passive"))
      (node (ref "C48") (pin "2") (pinfunction "2_2") (pintype "passive"))
      (node (ref "C49") (pin "2") (pinfunction "2_2") (pintype "passive"))
      (node (ref "C50") (pin "2") (pinfunction "2_2") (pintype "passive"))
      (node (ref "C51") (pin "2") (pinfunction "2_2") (pintype "passive"))
      (node (ref "C52") (pin "2") (pinfunction "2_2") (pintype "passive"))
      (node (ref "C53") (pin "1") (pinfunction "1_1") (pintype "passive"))
      (node (ref "D3") (pin "2") (pinfunction "2_2") (pintype "passive"))
      (node (ref "MCU") (pin "105") (pinfunction "VDDLDO_105") (pintype "power_in"))
      (node (ref "MCU") (pin "106") (pinfunction "VDD_106") (pintype "power_in"))
      (node (ref "MCU") (pin "119") (pinfunction "VDD_119") (pintype "power_in"))
      (node (ref "MCU") (pin "129") (pinfunction "VDD_129") (pintype "power_in"))
      (node (ref "MCU") (pin "13") (pinfunction "VDD_13") (pintype "power_in"))
      (node (ref "MCU") (pin "143") (pinfunction "VDDLDO_143") (pintype "power_in"))
      (node (ref "MCU") (pin "144") (pinfunction "VDD_144") (pintype "power_in"))
      (node (ref "MCU") (pin "16") (pinfunction "VDDSMPS_16") (pintype "power_in"))
      (node (ref "MCU") (pin "19") (pinfunction "VDD_19") (pintype "power_in"))
      (node (ref "MCU") (pin "32") (pinfunction "VDD_32") (pintype "power_in"))
      (node (ref "MCU") (pin "36") (pinfunction "VDDA_36") (pintype "power_in"))
      (node (ref "MCU") (pin "42") (pinfunction "VDD_42") (pintype "power_in"))
      (node (ref "MCU") (pin "56") (pinfunction "VDD_56") (pintype "power_in"))
      (node (ref "MCU") (pin "7") (pinfunction "VDD_7") (pintype "power_in"))
      (node (ref "MCU") (pin "70") (pinfunction "VDDLDO_70") (pintype "power_in"))
      (node (ref "MCU") (pin "71") (pinfunction "VDD_71") (pintype "power_in"))
      (node (ref "MCU") (pin "79") (pinfunction "VDD_79") (pintype "power_in"))
      (node (ref "MCU") (pin "8") (pinfunction "VBAT_8") (pintype "power_in"))
      (node (ref "MCU") (pin "91") (pinfunction "VDD33USB_91") (pintype "power_in"))
      (node (ref "MCU") (pin "92") (pinfunction "VDD_92") (pintype "power_in"))
      (node (ref "R11") (pin "2") (pinfunction "2_2") (pintype "passive"))
      (node (ref "R9") (pin "1") (pinfunction "1_1") (pintype "passive"))
      (node (ref "SW2") (pin "1") (pinfunction "1_1") (pintype "passive"))
      (node (ref "SWD") (pin "1") (pinfunction "1_1") (pintype "passive"))
    )
    (net (code "104") (name "GND") (class "Default")
      (node (ref "C30") (pin "1") (pinfunction "1_1") (pintype "passive"))
      (node (ref "C31") (pin "1") (pinfunction "1_1") (pintype "passive"))
      (node (ref "C32") (pin "1") (pinfunction "1_1") (pintype "passive"))
      (node (ref "C33") (pin "2") (pinfunction "2_2") (pintype "passive"))
      (node (ref "C34") (pin "1") (pinfunction "1_1") (pintype "passive"))
      (node (ref "C35") (pin "1") (pinfunction "1_1") (pintype "passive"))
      (node (ref "C36") (pin "1") (pinfunction "1_1") (pintype "passive"))
      (node (ref "C37") (pin "2") (pinfunction "2_2") (pintype "passive"))
      (node (ref "C38") (pin "2") (pinfunction "2_2") (pintype "passive"))
      (node (ref "C39") (pin "2") (pinfunction "2_2") (pintype "passive"))
      (node (ref "C40") (pin "1") (pinfunction "1_1") (pintype "passive"))
      (node (ref "C41") (pin "1") (pinfunction "1_1") (pintype "passive"))
      (node (ref "C42") (pin "1") (pinfunction "1_1") (pintype "passive"))
      (node (ref "C43") (pin "1") (pinfunction "1_1") (pintype "passive"))
      (node (ref "C44") (pin "1") (pinfunction "1_1") (pintype "passive"))
      (node (ref "C45") (pin "1") (pinfunction "1_1") (pintype "passive"))
      (node (ref "C46") (pin "1") (pinfunction "1_1") (pintype "passive"))
      (node (ref "C47") (pin "1") (pinfunction "1_1") (pintype "passive"))
      (node (ref "C48") (pin "1") (pinfunction "1_1") (pintype "passive"))
      (node (ref "C49") (pin "1") (pinfunction "1_1") (pintype "passive"))
      (node (ref "C50") (pin "1") (pinfunction "1_1") (pintype "passive"))
      (node (ref "C51") (pin "1") (pinfunction "1_1") (pintype "passive"))
      (node (ref "C52") (pin "1") (pinfunction "1_1") (pintype "passive"))
      (node (ref "C53") (pin "2") (pinfunction "2_2") (pintype "passive"))
      (node (ref "C54") (pin "1") (pinfunction "1_1") (pintype "passive"))
      (node (ref "D3") (pin "1") (pinfunction "1_1") (pintype "passive"))
      (node (ref "MCU") (pin "104") (pinfunction "VSS_104") (pintype "power_in"))
      (node (ref "MCU") (pin "118") (pinfunction "VSS_118") (pintype "power_in"))
      (node (ref "MCU") (pin "12") (pinfunction "VSS_12") (pintype "power_in"))
      (node (ref "MCU") (pin "128") (pinfunction "VSS_128") (pintype "power_in"))
      (node (ref "MCU") (pin "14") (pinfunction "VSSSMPS_14") (pintype "power_in"))
      (node (ref "MCU") (pin "141") (pinfunction "VSS_141") (pintype "power_in"))
      (node (ref "MCU") (pin "18") (pinfunction "VSS_18") (pintype "power_in"))
      (node (ref "MCU") (pin "33") (pinfunction "VSS_33") (pintype "power_in"))
      (node (ref "MCU") (pin "34") (pinfunction "VSSA_34") (pintype "power_in"))
      (node (ref "MCU") (pin "41") (pinfunction "VSS_41") (pintype "power_in"))
      (node (ref "MCU") (pin "55") (pinfunction "VSS_55") (pintype "power_in"))
      (node (ref "MCU") (pin "6") (pinfunction "VSS_6") (pintype "power_in"))
      (node (ref "MCU") (pin "69") (pinfunction "VSS_69") (pintype "power_in"))
      (node (ref "MCU") (pin "80") (pinfunction "VSS_80") (pintype "power_in"))
      (node (ref "MCU") (pin "89") (pinfunction "VSS_89") (pintype "power_in"))
      (node (ref "SW2") (pin "3") (pinfunction "3_3") (pintype "passive"))
      (node (ref "SW3") (pin "1") (pinfunction "1_1") (pintype "passive"))
      (node (ref "SW3") (pin "2") (pinfunction "2_2") (pintype "passive"))
      (node (ref "SWD") (pin "6") (pinfunction "6_6") (pintype "passive"))
    )
    (net (code "105") (name "Net-(MCUA-PDR_ON)") (class "Default")
      (node (ref "MCU") (pin "142") (pinfunction "PDR_ON_142") (pintype "bidirectional"))
      (node (ref "R11") (pin "1") (pinfunction "1_1") (pintype "passive"))
    )
    (net (code "106") (name "Net-(SW2-COM)") (class "Default")
      (node (ref "R10") (pin "2") (pinfunction "2_2") (pintype "passive"))
      (node (ref "SW2") (pin "2") (pinfunction "COM_2") (pintype "passive"))
    )
    (net (code "107") (name "VREF+") (class "Default")
      (node (ref "C30") (pin "2") (pinfunction "2_2") (pintype "passive"))
      (node (ref "C31") (pin "2") (pinfunction "2_2") (pintype "passive"))
      (node (ref "MCU") (pin "35") (pinfunction "VREF+_35") (pintype "power_in"))
      (node (ref "R9") (pin "2") (pinfunction "2_2") (pintype "passive"))
    )
    (net (code "108") (name "unconnected-(CONN4-Pad14)") (class "Default")
      (node (ref "CONN4") (pin "14") (pinfunction "14_14") (pintype "passive+no_connect"))
    )
    (net (code "109") (name "unconnected-(CONN6-Pad8)") (class "Default")
      (node (ref "CONN6") (pin "8") (pinfunction "8_8") (pintype "passive+no_connect"))
    )
    (net (code "110") (name "unconnected-(MCUC-VDD50USB-Pad90)") (class "Default")
      (node (ref "MCU") (pin "90") (pinfunction "VDD50USB_90") (pintype "power_in+no_connect"))
    )
    (net (code "111") (name "unconnected-(MCUC-VFBSMPS-Pad17)") (class "Default")
      (node (ref "MCU") (pin "17") (pinfunction "VFBSMPS_17") (pintype "power_in+no_connect"))
    )
    (net (code "112") (name "unconnected-(MCUC-VLXSMPS-Pad15)") (class "Default")
      (node (ref "MCU") (pin "15") (pinfunction "VLXSMPS_15") (pintype "power_in+no_connect"))
    )
  )
)
